# IOT_proje.net
KiCad netlist of a schematic drawn in EasyEDA
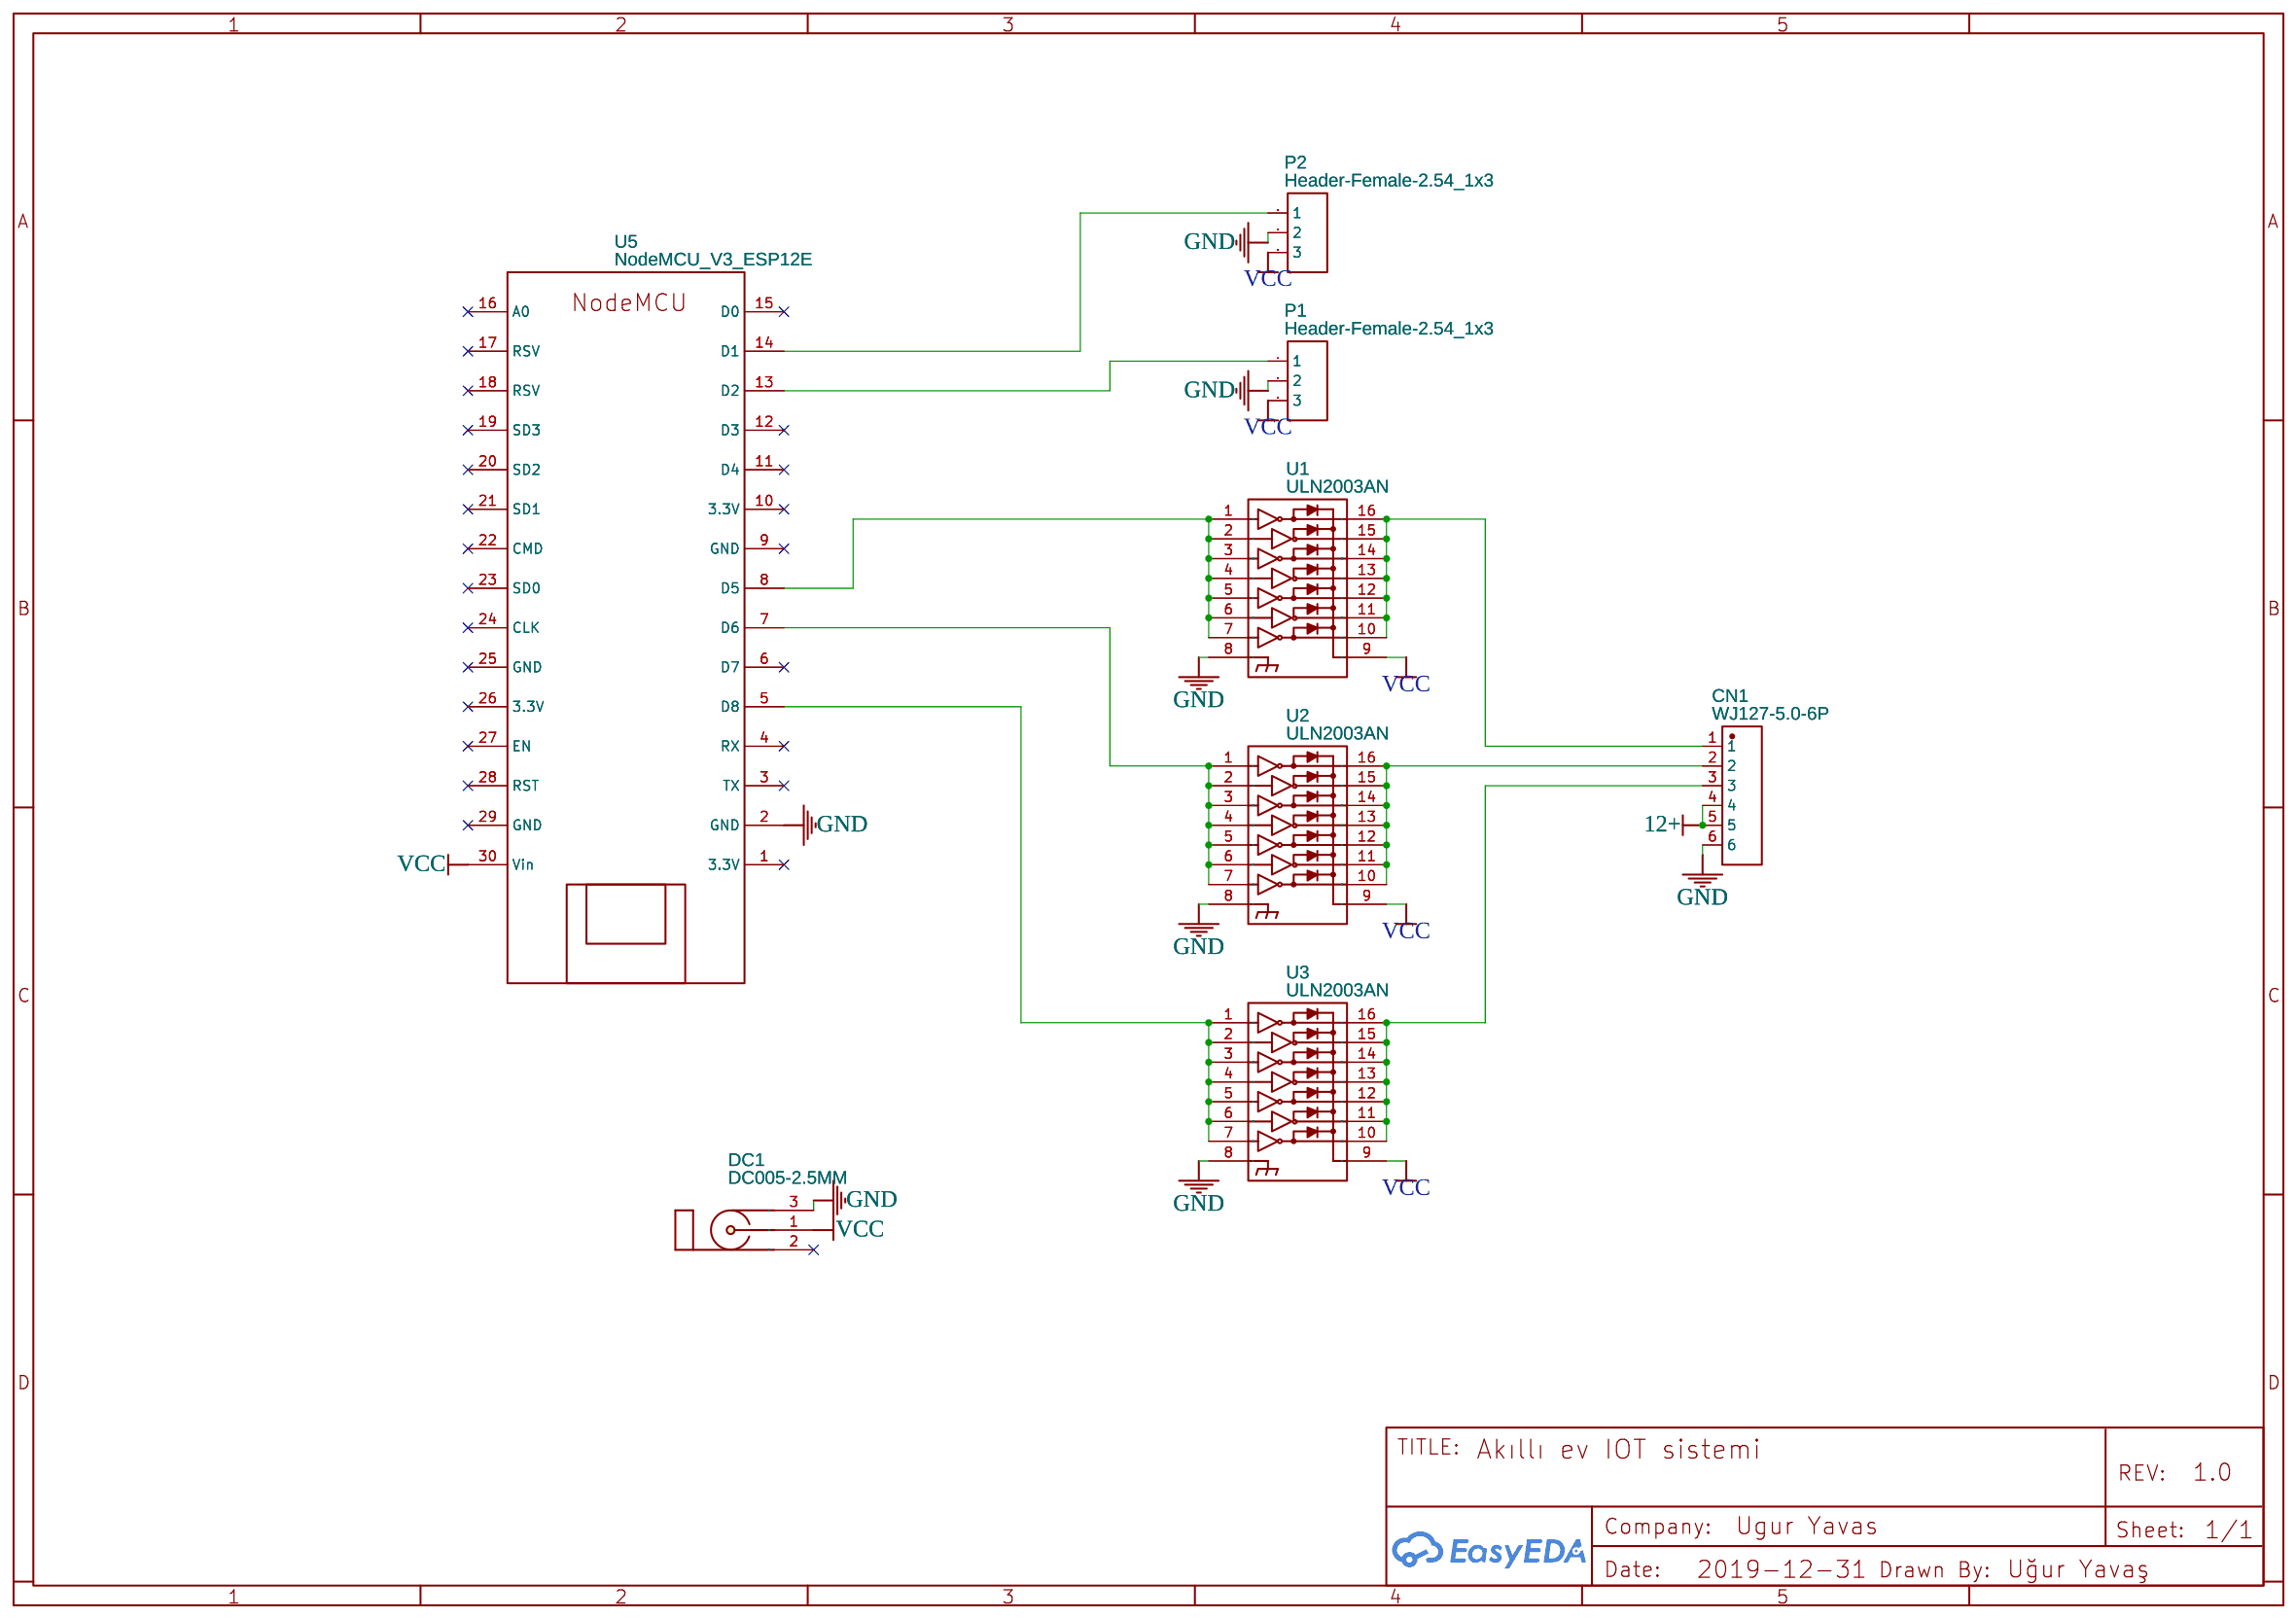
[diagram p0: schematic sheet]

(export (version "E")
  (design (tool "Eeschema 10.0.6"))
  (components
    (comp (ref "CN1")
      (value "WJ127-5.0-6P")
      (fields (field (name "BOM_Supplier Part") "C192781"))
      (libsource (lib "") (part "WJ127-5.0-6P"))
    )
    (comp (ref "DC1")
      (value "DC005-2.5MM")
      (fields (field (name "BOM_Supplier Part") "C111573"))
      (libsource (lib "") (part "DC005-2.5MM"))
    )
    (comp (ref "P1")
      (value "Header-Female-2.54_1x3")
      (fields (field (name "BOM_Supplier Part") "C146243"))
      (libsource (lib "") (part "Header-Female-2.54_1x3"))
    )
    (comp (ref "P2")
      (value "Header-Female-2.54_1x3")
      (fields (field (name "BOM_Supplier Part") "C146243"))
      (libsource (lib "") (part "Header-Female-2.54_1x3"))
    )
    (comp (ref "U1")
      (value "ULN2003AN")
      (fields (field (name "BOM_Supplier Part") "C90448"))
      (libsource (lib "") (part "ULN2003AN"))
    )
    (comp (ref "U2")
      (value "ULN2003AN")
      (fields (field (name "BOM_Supplier Part") "C90448"))
      (libsource (lib "") (part "ULN2003AN"))
    )
    (comp (ref "U3")
      (value "ULN2003AN")
      (fields (field (name "BOM_Supplier Part") "C90448"))
      (libsource (lib "") (part "ULN2003AN"))
    )
    (comp (ref "U5")
      (value "NodeMCU_V3_ESP12E")
      (fields (field (name "BOM_Manufacturer Part") "?"))
      (libsource (lib "") (part "NodeMCU_V1_ESP12E"))
    )
  )
  (nets
    (net (code "1") (name "12+") (class "Default")
      (node (ref "CN1") (pin "4") (pinfunction "4_4") (pintype "unspecified"))
      (node (ref "CN1") (pin "5") (pinfunction "5_5") (pintype "unspecified"))
    )
    (net (code "2") (name "GND") (class "Default")
      (node (ref "CN1") (pin "6") (pinfunction "6_6") (pintype "unspecified"))
      (node (ref "DC1") (pin "3") (pinfunction "3_3") (pintype "input"))
      (node (ref "P1") (pin "2") (pinfunction "2_2") (pintype "input"))
      (node (ref "P2") (pin "2") (pinfunction "2_2") (pintype "input"))
      (node (ref "U1") (pin "8") (pinfunction "E_8") (pintype "unspecified"))
      (node (ref "U2") (pin "8") (pinfunction "E_8") (pintype "unspecified"))
      (node (ref "U3") (pin "8") (pinfunction "E_8") (pintype "unspecified"))
      (node (ref "U5") (pin "2") (pinfunction "GND_2") (pintype "unspecified"))
    )
    (net (code "3") (name "Net-(U1-1B)") (class "Default")
      (node (ref "U1") (pin "1") (pinfunction "1B_1") (pintype "unspecified"))
      (node (ref "U1") (pin "2") (pinfunction "2B_2") (pintype "unspecified"))
      (node (ref "U1") (pin "3") (pinfunction "3B_3") (pintype "unspecified"))
      (node (ref "U1") (pin "4") (pinfunction "4B_4") (pintype "unspecified"))
      (node (ref "U1") (pin "5") (pinfunction "5B_5") (pintype "unspecified"))
      (node (ref "U1") (pin "6") (pinfunction "6B_6") (pintype "unspecified"))
      (node (ref "U1") (pin "7") (pinfunction "7B_7") (pintype "unspecified"))
      (node (ref "U5") (pin "8") (pinfunction "D5_8") (pintype "unspecified"))
    )
    (net (code "4") (name "Net-(U1-1C)") (class "Default")
      (node (ref "CN1") (pin "1") (pinfunction "1_1") (pintype "unspecified"))
      (node (ref "U1") (pin "10") (pinfunction "7C_10") (pintype "unspecified"))
      (node (ref "U1") (pin "11") (pinfunction "6C_11") (pintype "unspecified"))
      (node (ref "U1") (pin "12") (pinfunction "5C_12") (pintype "unspecified"))
      (node (ref "U1") (pin "13") (pinfunction "4C_13") (pintype "unspecified"))
      (node (ref "U1") (pin "14") (pinfunction "3C_14") (pintype "unspecified"))
      (node (ref "U1") (pin "15") (pinfunction "2C_15") (pintype "unspecified"))
      (node (ref "U1") (pin "16") (pinfunction "1C_16") (pintype "unspecified"))
    )
    (net (code "5") (name "Net-(U2-1B)") (class "Default")
      (node (ref "U2") (pin "1") (pinfunction "1B_1") (pintype "unspecified"))
      (node (ref "U2") (pin "2") (pinfunction "2B_2") (pintype "unspecified"))
      (node (ref "U2") (pin "3") (pinfunction "3B_3") (pintype "unspecified"))
      (node (ref "U2") (pin "4") (pinfunction "4B_4") (pintype "unspecified"))
      (node (ref "U2") (pin "5") (pinfunction "5B_5") (pintype "unspecified"))
      (node (ref "U2") (pin "6") (pinfunction "6B_6") (pintype "unspecified"))
      (node (ref "U2") (pin "7") (pinfunction "7B_7") (pintype "unspecified"))
      (node (ref "U5") (pin "7") (pinfunction "D6_7") (pintype "unspecified"))
    )
    (net (code "6") (name "Net-(U2-1C)") (class "Default")
      (node (ref "CN1") (pin "2") (pinfunction "2_2") (pintype "unspecified"))
      (node (ref "U2") (pin "10") (pinfunction "7C_10") (pintype "unspecified"))
      (node (ref "U2") (pin "11") (pinfunction "6C_11") (pintype "unspecified"))
      (node (ref "U2") (pin "12") (pinfunction "5C_12") (pintype "unspecified"))
      (node (ref "U2") (pin "13") (pinfunction "4C_13") (pintype "unspecified"))
      (node (ref "U2") (pin "14") (pinfunction "3C_14") (pintype "unspecified"))
      (node (ref "U2") (pin "15") (pinfunction "2C_15") (pintype "unspecified"))
      (node (ref "U2") (pin "16") (pinfunction "1C_16") (pintype "unspecified"))
    )
    (net (code "7") (name "Net-(U3-1B)") (class "Default")
      (node (ref "U3") (pin "1") (pinfunction "1B_1") (pintype "unspecified"))
      (node (ref "U3") (pin "2") (pinfunction "2B_2") (pintype "unspecified"))
      (node (ref "U3") (pin "3") (pinfunction "3B_3") (pintype "unspecified"))
      (node (ref "U3") (pin "4") (pinfunction "4B_4") (pintype "unspecified"))
      (node (ref "U3") (pin "5") (pinfunction "5B_5") (pintype "unspecified"))
      (node (ref "U3") (pin "6") (pinfunction "6B_6") (pintype "unspecified"))
      (node (ref "U3") (pin "7") (pinfunction "7B_7") (pintype "unspecified"))
      (node (ref "U5") (pin "5") (pinfunction "D8_5") (pintype "unspecified"))
    )
    (net (code "8") (name "Net-(U3-1C)") (class "Default")
      (node (ref "CN1") (pin "3") (pinfunction "3_3") (pintype "unspecified"))
      (node (ref "U3") (pin "10") (pinfunction "7C_10") (pintype "unspecified"))
      (node (ref "U3") (pin "11") (pinfunction "6C_11") (pintype "unspecified"))
      (node (ref "U3") (pin "12") (pinfunction "5C_12") (pintype "unspecified"))
      (node (ref "U3") (pin "13") (pinfunction "4C_13") (pintype "unspecified"))
      (node (ref "U3") (pin "14") (pinfunction "3C_14") (pintype "unspecified"))
      (node (ref "U3") (pin "15") (pinfunction "2C_15") (pintype "unspecified"))
      (node (ref "U3") (pin "16") (pinfunction "1C_16") (pintype "unspecified"))
    )
    (net (code "9") (name "Net-(U5-D1)") (class "Default")
      (node (ref "P2") (pin "1") (pinfunction "1_1") (pintype "input"))
      (node (ref "U5") (pin "14") (pinfunction "D1_14") (pintype "unspecified"))
    )
    (net (code "10") (name "Net-(U5-D2)") (class "Default")
      (node (ref "P1") (pin "1") (pinfunction "1_1") (pintype "input"))
      (node (ref "U5") (pin "13") (pinfunction "D2_13") (pintype "unspecified"))
    )
    (net (code "11") (name "VCC") (class "Default")
      (node (ref "DC1") (pin "1") (pinfunction "VCC_1") (pintype "input"))
      (node (ref "P1") (pin "3") (pinfunction "3_3") (pintype "input"))
      (node (ref "P2") (pin "3") (pinfunction "3_3") (pintype "input"))
      (node (ref "U1") (pin "9") (pinfunction "COM_9") (pintype "unspecified"))
      (node (ref "U2") (pin "9") (pinfunction "COM_9") (pintype "unspecified"))
      (node (ref "U3") (pin "9") (pinfunction "COM_9") (pintype "unspecified"))
      (node (ref "U5") (pin "30") (pinfunction "Vin_30") (pintype "unspecified"))
    )
    (net (code "12") (name "unconnected-(DC1-Pad2)") (class "Default")
      (node (ref "DC1") (pin "2") (pinfunction "2_2") (pintype "input+no_connect"))
    )
    (net (code "13") (name "unconnected-(U5-3.3V-Pad1)") (class "Default")
      (node (ref "U5") (pin "1") (pinfunction "3.3V_1") (pintype "unspecified+no_connect"))
    )
    (net (code "14") (name "unconnected-(U5-3.3V-Pad10)") (class "Default")
      (node (ref "U5") (pin "10") (pinfunction "3.3V_10") (pintype "unspecified+no_connect"))
    )
    (net (code "15") (name "unconnected-(U5-3.3V-Pad26)") (class "Default")
      (node (ref "U5") (pin "26") (pinfunction "3.3V_26") (pintype "unspecified+no_connect"))
    )
    (net (code "16") (name "unconnected-(U5-A0-Pad16)") (class "Default")
      (node (ref "U5") (pin "16") (pinfunction "A0_16") (pintype "unspecified+no_connect"))
    )
    (net (code "17") (name "unconnected-(U5-CLK-Pad24)") (class "Default")
      (node (ref "U5") (pin "24") (pinfunction "CLK_24") (pintype "unspecified+no_connect"))
    )
    (net (code "18") (name "unconnected-(U5-CMD-Pad22)") (class "Default")
      (node (ref "U5") (pin "22") (pinfunction "CMD_22") (pintype "unspecified+no_connect"))
    )
    (net (code "19") (name "unconnected-(U5-D0-Pad15)") (class "Default")
      (node (ref "U5") (pin "15") (pinfunction "D0_15") (pintype "unspecified+no_connect"))
    )
    (net (code "20") (name "unconnected-(U5-D3-Pad12)") (class "Default")
      (node (ref "U5") (pin "12") (pinfunction "D3_12") (pintype "unspecified+no_connect"))
    )
    (net (code "21") (name "unconnected-(U5-D4-Pad11)") (class "Default")
      (node (ref "U5") (pin "11") (pinfunction "D4_11") (pintype "unspecified+no_connect"))
    )
    (net (code "22") (name "unconnected-(U5-D7-Pad6)") (class "Default")
      (node (ref "U5") (pin "6") (pinfunction "D7_6") (pintype "unspecified+no_connect"))
    )
    (net (code "23") (name "unconnected-(U5-EN-Pad27)") (class "Default")
      (node (ref "U5") (pin "27") (pinfunction "EN_27") (pintype "unspecified+no_connect"))
    )
    (net (code "24") (name "unconnected-(U5-GND-Pad9)") (class "Default")
      (node (ref "U5") (pin "9") (pinfunction "GND_9") (pintype "unspecified+no_connect"))
    )
    (net (code "25") (name "unconnected-(U5-GND-Pad25)") (class "Default")
      (node (ref "U5") (pin "25") (pinfunction "GND_25") (pintype "unspecified+no_connect"))
    )
    (net (code "26") (name "unconnected-(U5-GND-Pad29)") (class "Default")
      (node (ref "U5") (pin "29") (pinfunction "GND_29") (pintype "unspecified+no_connect"))
    )
    (net (code "27") (name "unconnected-(U5-RST-Pad28)") (class "Default")
      (node (ref "U5") (pin "28") (pinfunction "RST_28") (pintype "unspecified+no_connect"))
    )
    (net (code "28") (name "unconnected-(U5-RSV-Pad17)") (class "Default")
      (node (ref "U5") (pin "17") (pinfunction "RSV_17") (pintype "unspecified+no_connect"))
    )
    (net (code "29") (name "unconnected-(U5-RSV-Pad18)") (class "Default")
      (node (ref "U5") (pin "18") (pinfunction "RSV_18") (pintype "unspecified+no_connect"))
    )
    (net (code "30") (name "unconnected-(U5-RX-Pad4)") (class "Default")
      (node (ref "U5") (pin "4") (pinfunction "RX_4") (pintype "unspecified+no_connect"))
    )
    (net (code "31") (name "unconnected-(U5-SD0-Pad23)") (class "Default")
      (node (ref "U5") (pin "23") (pinfunction "SD0_23") (pintype "unspecified+no_connect"))
    )
    (net (code "32") (name "unconnected-(U5-SD1-Pad21)") (class "Default")
      (node (ref "U5") (pin "21") (pinfunction "SD1_21") (pintype "unspecified+no_connect"))
    )
    (net (code "33") (name "unconnected-(U5-SD2-Pad20)") (class "Default")
      (node (ref "U5") (pin "20") (pinfunction "SD2_20") (pintype "unspecified+no_connect"))
    )
    (net (code "34") (name "unconnected-(U5-SD3-Pad19)") (class "Default")
      (node (ref "U5") (pin "19") (pinfunction "SD3_19") (pintype "unspecified+no_connect"))
    )
    (net (code "35") (name "unconnected-(U5-TX-Pad3)") (class "Default")
      (node (ref "U5") (pin "3") (pinfunction "TX_3") (pintype "unspecified+no_connect"))
    )
  )
)
